# flex_adapter.net
KiCad netlist of a schematic drawn in EAGLE
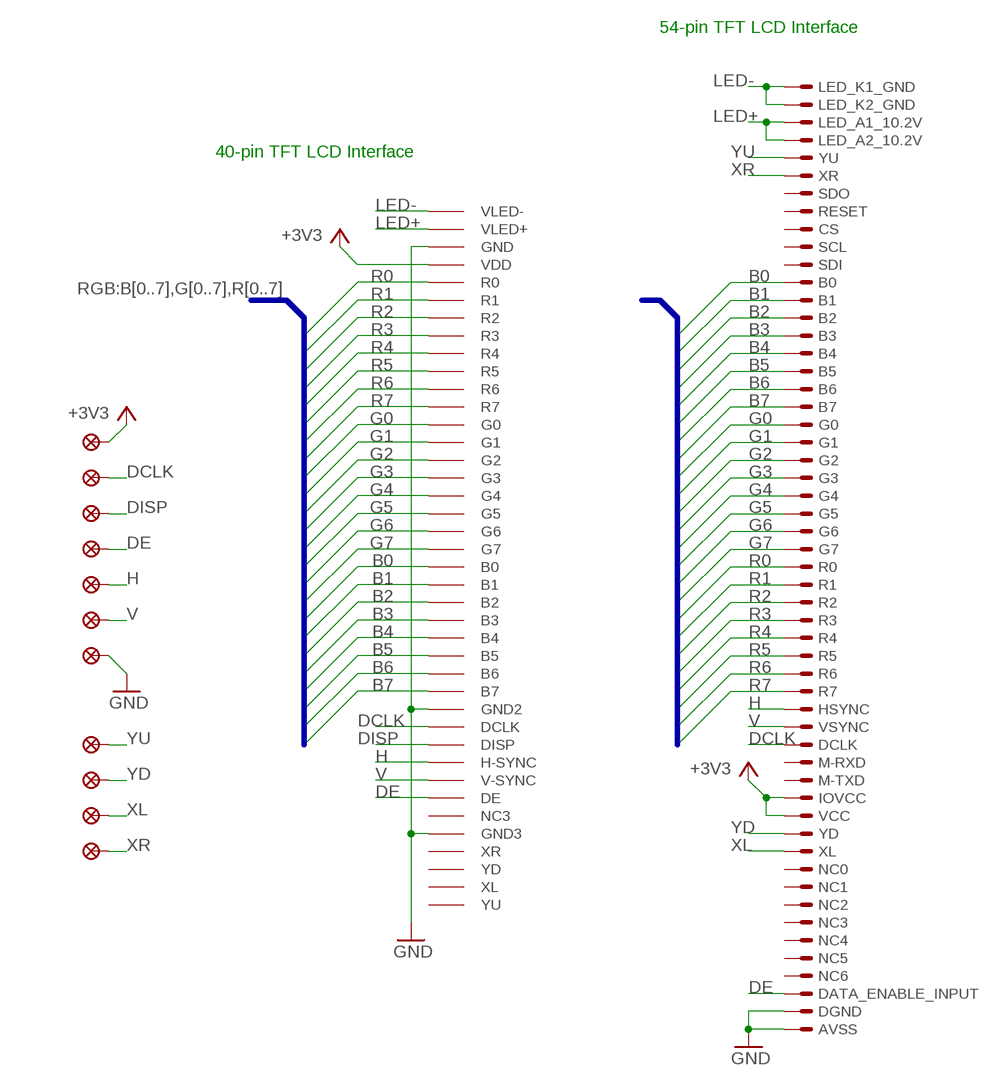
[diagram p0: schematic, sheet 1]

(export (version "E")
  (design (tool "Eeschema 10.0.6"))
  (components
    (comp (ref "U$1")
      (value "51296-5494")
      (footprint "eagle-import:51296")
      (fields (field (name "MF") "Molex"))
      (libsource (lib "eagle-import") (part "51296-5494"))
    )
    (comp (ref "U$2")
      (value "40PIN")
      (footprint "eagle-import:40PIN")
      (libsource (lib "eagle-import") (part "40PIN"))
    )
    (comp (ref "U$3")
      (value "TESTPAD")
      (footprint "eagle-import:SOLDERPAD")
      (libsource (lib "eagle-import") (part "TESTPAD"))
    )
    (comp (ref "U$4")
      (value "TESTPAD")
      (footprint "eagle-import:SOLDERPAD")
      (libsource (lib "eagle-import") (part "TESTPAD"))
    )
    (comp (ref "U$5")
      (value "TESTPAD")
      (footprint "eagle-import:SOLDERPAD")
      (libsource (lib "eagle-import") (part "TESTPAD"))
    )
    (comp (ref "U$6")
      (value "TESTPAD")
      (footprint "eagle-import:SOLDERPAD")
      (libsource (lib "eagle-import") (part "TESTPAD"))
    )
    (comp (ref "U$7")
      (value "TESTPAD")
      (footprint "eagle-import:SOLDERPAD")
      (libsource (lib "eagle-import") (part "TESTPAD"))
    )
    (comp (ref "U$8")
      (value "TESTPAD")
      (footprint "eagle-import:SOLDERPAD")
      (libsource (lib "eagle-import") (part "TESTPAD"))
    )
    (comp (ref "U$9")
      (value "TESTPAD")
      (footprint "eagle-import:SOLDERPAD")
      (libsource (lib "eagle-import") (part "TESTPAD"))
    )
    (comp (ref "U$10")
      (value "TESTPAD")
      (footprint "eagle-import:SOLDERPAD")
      (libsource (lib "eagle-import") (part "TESTPAD"))
    )
    (comp (ref "U$11")
      (value "TESTPAD")
      (footprint "eagle-import:SOLDERPAD")
      (libsource (lib "eagle-import") (part "TESTPAD"))
    )
    (comp (ref "U$12")
      (value "TESTPAD")
      (footprint "eagle-import:SOLDERPAD")
      (libsource (lib "eagle-import") (part "TESTPAD"))
    )
    (comp (ref "U$13")
      (value "TESTPAD")
      (footprint "eagle-import:SOLDERPAD")
      (libsource (lib "eagle-import") (part "TESTPAD"))
    )
  )
  (nets
    (net (code "1") (name "+3V3") (class "Default")
      (node (ref "U$1") (pin "41") (pinfunction "IOVCC_41") (pintype "passive"))
      (node (ref "U$1") (pin "42") (pinfunction "VCC_42") (pintype "passive"))
      (node (ref "U$2") (pin "P$4") (pinfunction "VDD_P$4") (pintype "bidirectional"))
      (node (ref "U$4") (pin "P$1") (pinfunction "P$1_P$1") (pintype "bidirectional"))
    )
    (net (code "2") (name "/B0") (class "Default")
      (node (ref "U$1") (pin "12") (pinfunction "B0_12") (pintype "passive"))
      (node (ref "U$2") (pin "P$21") (pinfunction "B0_P$21") (pintype "bidirectional"))
    )
    (net (code "3") (name "/B1") (class "Default")
      (node (ref "U$1") (pin "13") (pinfunction "B1_13") (pintype "passive"))
      (node (ref "U$2") (pin "P$22") (pinfunction "B1_P$22") (pintype "bidirectional"))
    )
    (net (code "4") (name "/B2") (class "Default")
      (node (ref "U$1") (pin "14") (pinfunction "B2_14") (pintype "passive"))
      (node (ref "U$2") (pin "P$23") (pinfunction "B2_P$23") (pintype "bidirectional"))
    )
    (net (code "5") (name "/B3") (class "Default")
      (node (ref "U$1") (pin "15") (pinfunction "B3_15") (pintype "passive"))
      (node (ref "U$2") (pin "P$24") (pinfunction "B3_P$24") (pintype "bidirectional"))
    )
    (net (code "6") (name "/B4") (class "Default")
      (node (ref "U$1") (pin "16") (pinfunction "B4_16") (pintype "passive"))
      (node (ref "U$2") (pin "P$25") (pinfunction "B4_P$25") (pintype "bidirectional"))
    )
    (net (code "7") (name "/B5") (class "Default")
      (node (ref "U$1") (pin "17") (pinfunction "B5_17") (pintype "passive"))
      (node (ref "U$2") (pin "P$26") (pinfunction "B5_P$26") (pintype "bidirectional"))
    )
    (net (code "8") (name "/B6") (class "Default")
      (node (ref "U$1") (pin "18") (pinfunction "B6_18") (pintype "passive"))
      (node (ref "U$2") (pin "P$27") (pinfunction "B6_P$27") (pintype "bidirectional"))
    )
    (net (code "9") (name "/B7") (class "Default")
      (node (ref "U$1") (pin "19") (pinfunction "B7_19") (pintype "passive"))
      (node (ref "U$2") (pin "P$28") (pinfunction "B7_P$28") (pintype "bidirectional"))
    )
    (net (code "10") (name "/DCLK") (class "Default")
      (node (ref "U$1") (pin "38") (pinfunction "DCLK_38") (pintype "passive"))
      (node (ref "U$2") (pin "P$30") (pinfunction "DCLK_P$30") (pintype "bidirectional"))
      (node (ref "U$8") (pin "P$1") (pinfunction "P$1_P$1") (pintype "bidirectional"))
    )
    (net (code "11") (name "/DE") (class "Default")
      (node (ref "U$1") (pin "52") (pinfunction "DATA_ENABLE_INPUT_52") (pintype "passive"))
      (node (ref "U$2") (pin "P$34") (pinfunction "DE_P$34") (pintype "bidirectional"))
      (node (ref "U$6") (pin "P$1") (pinfunction "P$1_P$1") (pintype "bidirectional"))
    )
    (net (code "12") (name "/DISP") (class "Default")
      (node (ref "U$2") (pin "P$31") (pinfunction "DISP_P$31") (pintype "bidirectional"))
      (node (ref "U$7") (pin "P$1") (pinfunction "P$1_P$1") (pintype "bidirectional"))
    )
    (net (code "13") (name "/G0") (class "Default")
      (node (ref "U$1") (pin "20") (pinfunction "G0_20") (pintype "passive"))
      (node (ref "U$2") (pin "P$13") (pinfunction "G0_P$13") (pintype "bidirectional"))
    )
    (net (code "14") (name "/G1") (class "Default")
      (node (ref "U$1") (pin "21") (pinfunction "G1_21") (pintype "passive"))
      (node (ref "U$2") (pin "P$14") (pinfunction "G1_P$14") (pintype "bidirectional"))
    )
    (net (code "15") (name "/G2") (class "Default")
      (node (ref "U$1") (pin "22") (pinfunction "G2_22") (pintype "passive"))
      (node (ref "U$2") (pin "P$15") (pinfunction "G2_P$15") (pintype "bidirectional"))
    )
    (net (code "16") (name "/G3") (class "Default")
      (node (ref "U$1") (pin "23") (pinfunction "G3_23") (pintype "passive"))
      (node (ref "U$2") (pin "P$16") (pinfunction "G3_P$16") (pintype "bidirectional"))
    )
    (net (code "17") (name "/G4") (class "Default")
      (node (ref "U$1") (pin "24") (pinfunction "G4_24") (pintype "passive"))
      (node (ref "U$2") (pin "P$17") (pinfunction "G4_P$17") (pintype "bidirectional"))
    )
    (net (code "18") (name "/G5") (class "Default")
      (node (ref "U$1") (pin "25") (pinfunction "G5_25") (pintype "passive"))
      (node (ref "U$2") (pin "P$18") (pinfunction "G5_P$18") (pintype "bidirectional"))
    )
    (net (code "19") (name "/G6") (class "Default")
      (node (ref "U$1") (pin "26") (pinfunction "G6_26") (pintype "passive"))
      (node (ref "U$2") (pin "P$19") (pinfunction "G6_P$19") (pintype "bidirectional"))
    )
    (net (code "20") (name "/G7") (class "Default")
      (node (ref "U$1") (pin "27") (pinfunction "G7_27") (pintype "passive"))
      (node (ref "U$2") (pin "P$20") (pinfunction "G7_P$20") (pintype "bidirectional"))
    )
    (net (code "21") (name "/H") (class "Default")
      (node (ref "U$1") (pin "36") (pinfunction "HSYNC_36") (pintype "passive"))
      (node (ref "U$2") (pin "P$32") (pinfunction "H-SYNC_P$32") (pintype "bidirectional"))
      (node (ref "U$5") (pin "P$1") (pinfunction "P$1_P$1") (pintype "bidirectional"))
    )
    (net (code "22") (name "/LED+") (class "Default")
      (node (ref "U$1") (pin "3") (pinfunction "LED_A1_10.2V_3") (pintype "passive"))
      (node (ref "U$1") (pin "4") (pinfunction "LED_A2_10.2V_4") (pintype "passive"))
      (node (ref "U$2") (pin "P$2") (pinfunction "VLED+_P$2") (pintype "bidirectional"))
    )
    (net (code "23") (name "/LED-") (class "Default")
      (node (ref "U$1") (pin "1") (pinfunction "LED_K1_GND_1") (pintype "passive"))
      (node (ref "U$1") (pin "2") (pinfunction "LED_K2_GND_2") (pintype "passive"))
      (node (ref "U$2") (pin "P$1") (pinfunction "VLED-_P$1") (pintype "bidirectional"))
    )
    (net (code "24") (name "/R0") (class "Default")
      (node (ref "U$1") (pin "28") (pinfunction "R0_28") (pintype "passive"))
      (node (ref "U$2") (pin "P$5") (pinfunction "R0_P$5") (pintype "bidirectional"))
    )
    (net (code "25") (name "/R1") (class "Default")
      (node (ref "U$1") (pin "29") (pinfunction "R1_29") (pintype "passive"))
      (node (ref "U$2") (pin "P$6") (pinfunction "R1_P$6") (pintype "bidirectional"))
    )
    (net (code "26") (name "/R2") (class "Default")
      (node (ref "U$1") (pin "30") (pinfunction "R2_30") (pintype "passive"))
      (node (ref "U$2") (pin "P$7") (pinfunction "R2_P$7") (pintype "bidirectional"))
    )
    (net (code "27") (name "/R3") (class "Default")
      (node (ref "U$1") (pin "31") (pinfunction "R3_31") (pintype "passive"))
      (node (ref "U$2") (pin "P$8") (pinfunction "R3_P$8") (pintype "bidirectional"))
    )
    (net (code "28") (name "/R4") (class "Default")
      (node (ref "U$1") (pin "32") (pinfunction "R4_32") (pintype "passive"))
      (node (ref "U$2") (pin "P$9") (pinfunction "R4_P$9") (pintype "bidirectional"))
    )
    (net (code "29") (name "/R5") (class "Default")
      (node (ref "U$1") (pin "33") (pinfunction "R5_33") (pintype "passive"))
      (node (ref "U$2") (pin "P$10") (pinfunction "R5_P$10") (pintype "bidirectional"))
    )
    (net (code "30") (name "/R6") (class "Default")
      (node (ref "U$1") (pin "34") (pinfunction "R6_34") (pintype "passive"))
      (node (ref "U$2") (pin "P$11") (pinfunction "R6_P$11") (pintype "bidirectional"))
    )
    (net (code "31") (name "/R7") (class "Default")
      (node (ref "U$1") (pin "35") (pinfunction "R7_35") (pintype "passive"))
      (node (ref "U$2") (pin "P$12") (pinfunction "R7_P$12") (pintype "bidirectional"))
    )
    (net (code "32") (name "/V") (class "Default")
      (node (ref "U$1") (pin "37") (pinfunction "VSYNC_37") (pintype "passive"))
      (node (ref "U$2") (pin "P$33") (pinfunction "V-SYNC_P$33") (pintype "bidirectional"))
      (node (ref "U$3") (pin "P$1") (pinfunction "P$1_P$1") (pintype "bidirectional"))
    )
    (net (code "33") (name "/XL") (class "Default")
      (node (ref "U$1") (pin "44") (pinfunction "XL_44") (pintype "passive"))
      (node (ref "U$12") (pin "P$1") (pinfunction "P$1_P$1") (pintype "bidirectional"))
    )
    (net (code "34") (name "/XR") (class "Default")
      (node (ref "U$1") (pin "6") (pinfunction "XR_6") (pintype "passive"))
      (node (ref "U$13") (pin "P$1") (pinfunction "P$1_P$1") (pintype "bidirectional"))
    )
    (net (code "35") (name "/YD") (class "Default")
      (node (ref "U$1") (pin "43") (pinfunction "YD_43") (pintype "passive"))
      (node (ref "U$11") (pin "P$1") (pinfunction "P$1_P$1") (pintype "bidirectional"))
    )
    (net (code "36") (name "/YU") (class "Default")
      (node (ref "U$1") (pin "5") (pinfunction "YU_5") (pintype "passive"))
      (node (ref "U$10") (pin "P$1") (pinfunction "P$1_P$1") (pintype "bidirectional"))
    )
    (net (code "38") (name "GND") (class "Default")
      (node (ref "U$1") (pin "53") (pinfunction "DGND_53") (pintype "passive"))
      (node (ref "U$1") (pin "54") (pinfunction "AVSS_54") (pintype "passive"))
      (node (ref "U$2") (pin "P$29") (pinfunction "GND2_P$29") (pintype "bidirectional"))
      (node (ref "U$2") (pin "P$3") (pinfunction "GND_P$3") (pintype "bidirectional"))
      (node (ref "U$2") (pin "P$36") (pinfunction "GND3_P$36") (pintype "bidirectional"))
      (node (ref "U$9") (pin "P$1") (pinfunction "P$1_P$1") (pintype "bidirectional"))
    )
    (net (code "39") (name "unconnected-(U$1-CS-Pad9)") (class "Default")
      (node (ref "U$1") (pin "9") (pinfunction "CS_9") (pintype "passive"))
    )
    (net (code "40") (name "unconnected-(U$1-M-RXD-Pad39)") (class "Default")
      (node (ref "U$1") (pin "39") (pinfunction "M-RXD_39") (pintype "passive"))
    )
    (net (code "41") (name "unconnected-(U$1-M-TXD-Pad40)") (class "Default")
      (node (ref "U$1") (pin "40") (pinfunction "M-TXD_40") (pintype "passive"))
    )
    (net (code "42") (name "unconnected-(U$1-NC0-Pad45)") (class "Default")
      (node (ref "U$1") (pin "45") (pinfunction "NC0_45") (pintype "passive"))
    )
    (net (code "43") (name "unconnected-(U$1-NC1-Pad46)") (class "Default")
      (node (ref "U$1") (pin "46") (pinfunction "NC1_46") (pintype "passive"))
    )
    (net (code "44") (name "unconnected-(U$1-NC2-Pad47)") (class "Default")
      (node (ref "U$1") (pin "47") (pinfunction "NC2_47") (pintype "passive"))
    )
    (net (code "45") (name "unconnected-(U$1-NC3-Pad48)") (class "Default")
      (node (ref "U$1") (pin "48") (pinfunction "NC3_48") (pintype "passive"))
    )
    (net (code "46") (name "unconnected-(U$1-NC4-Pad49)") (class "Default")
      (node (ref "U$1") (pin "49") (pinfunction "NC4_49") (pintype "passive"))
    )
    (net (code "47") (name "unconnected-(U$1-NC5-Pad50)") (class "Default")
      (node (ref "U$1") (pin "50") (pinfunction "NC5_50") (pintype "passive"))
    )
    (net (code "48") (name "unconnected-(U$1-NC6-Pad51)") (class "Default")
      (node (ref "U$1") (pin "51") (pinfunction "NC6_51") (pintype "passive"))
    )
    (net (code "49") (name "unconnected-(U$1-RESET-Pad8)") (class "Default")
      (node (ref "U$1") (pin "8") (pinfunction "RESET_8") (pintype "passive"))
    )
    (net (code "50") (name "unconnected-(U$1-SCL-Pad10)") (class "Default")
      (node (ref "U$1") (pin "10") (pinfunction "SCL_10") (pintype "passive"))
    )
    (net (code "51") (name "unconnected-(U$1-SDI-Pad11)") (class "Default")
      (node (ref "U$1") (pin "11") (pinfunction "SDI_11") (pintype "passive"))
    )
    (net (code "52") (name "unconnected-(U$1-SDO-Pad7)") (class "Default")
      (node (ref "U$1") (pin "7") (pinfunction "SDO_7") (pintype "passive"))
    )
    (net (code "53") (name "unconnected-(U$2-NC3-PadP$35)") (class "Default")
      (node (ref "U$2") (pin "P$35") (pinfunction "NC3_P$35") (pintype "bidirectional"))
    )
    (net (code "54") (name "unconnected-(U$2-XL-PadP$39)") (class "Default")
      (node (ref "U$2") (pin "P$39") (pinfunction "XL_P$39") (pintype "bidirectional"))
    )
    (net (code "55") (name "unconnected-(U$2-XR-PadP$37)") (class "Default")
      (node (ref "U$2") (pin "P$37") (pinfunction "XR_P$37") (pintype "bidirectional"))
    )
    (net (code "56") (name "unconnected-(U$2-YD-PadP$38)") (class "Default")
      (node (ref "U$2") (pin "P$38") (pinfunction "YD_P$38") (pintype "bidirectional"))
    )
    (net (code "57") (name "unconnected-(U$2-YU-PadP$40)") (class "Default")
      (node (ref "U$2") (pin "P$40") (pinfunction "YU_P$40") (pintype "bidirectional"))
    )
  )
)
